# adc-peripheral.net
KiCad netlist of a schematic drawn in Altium Designer
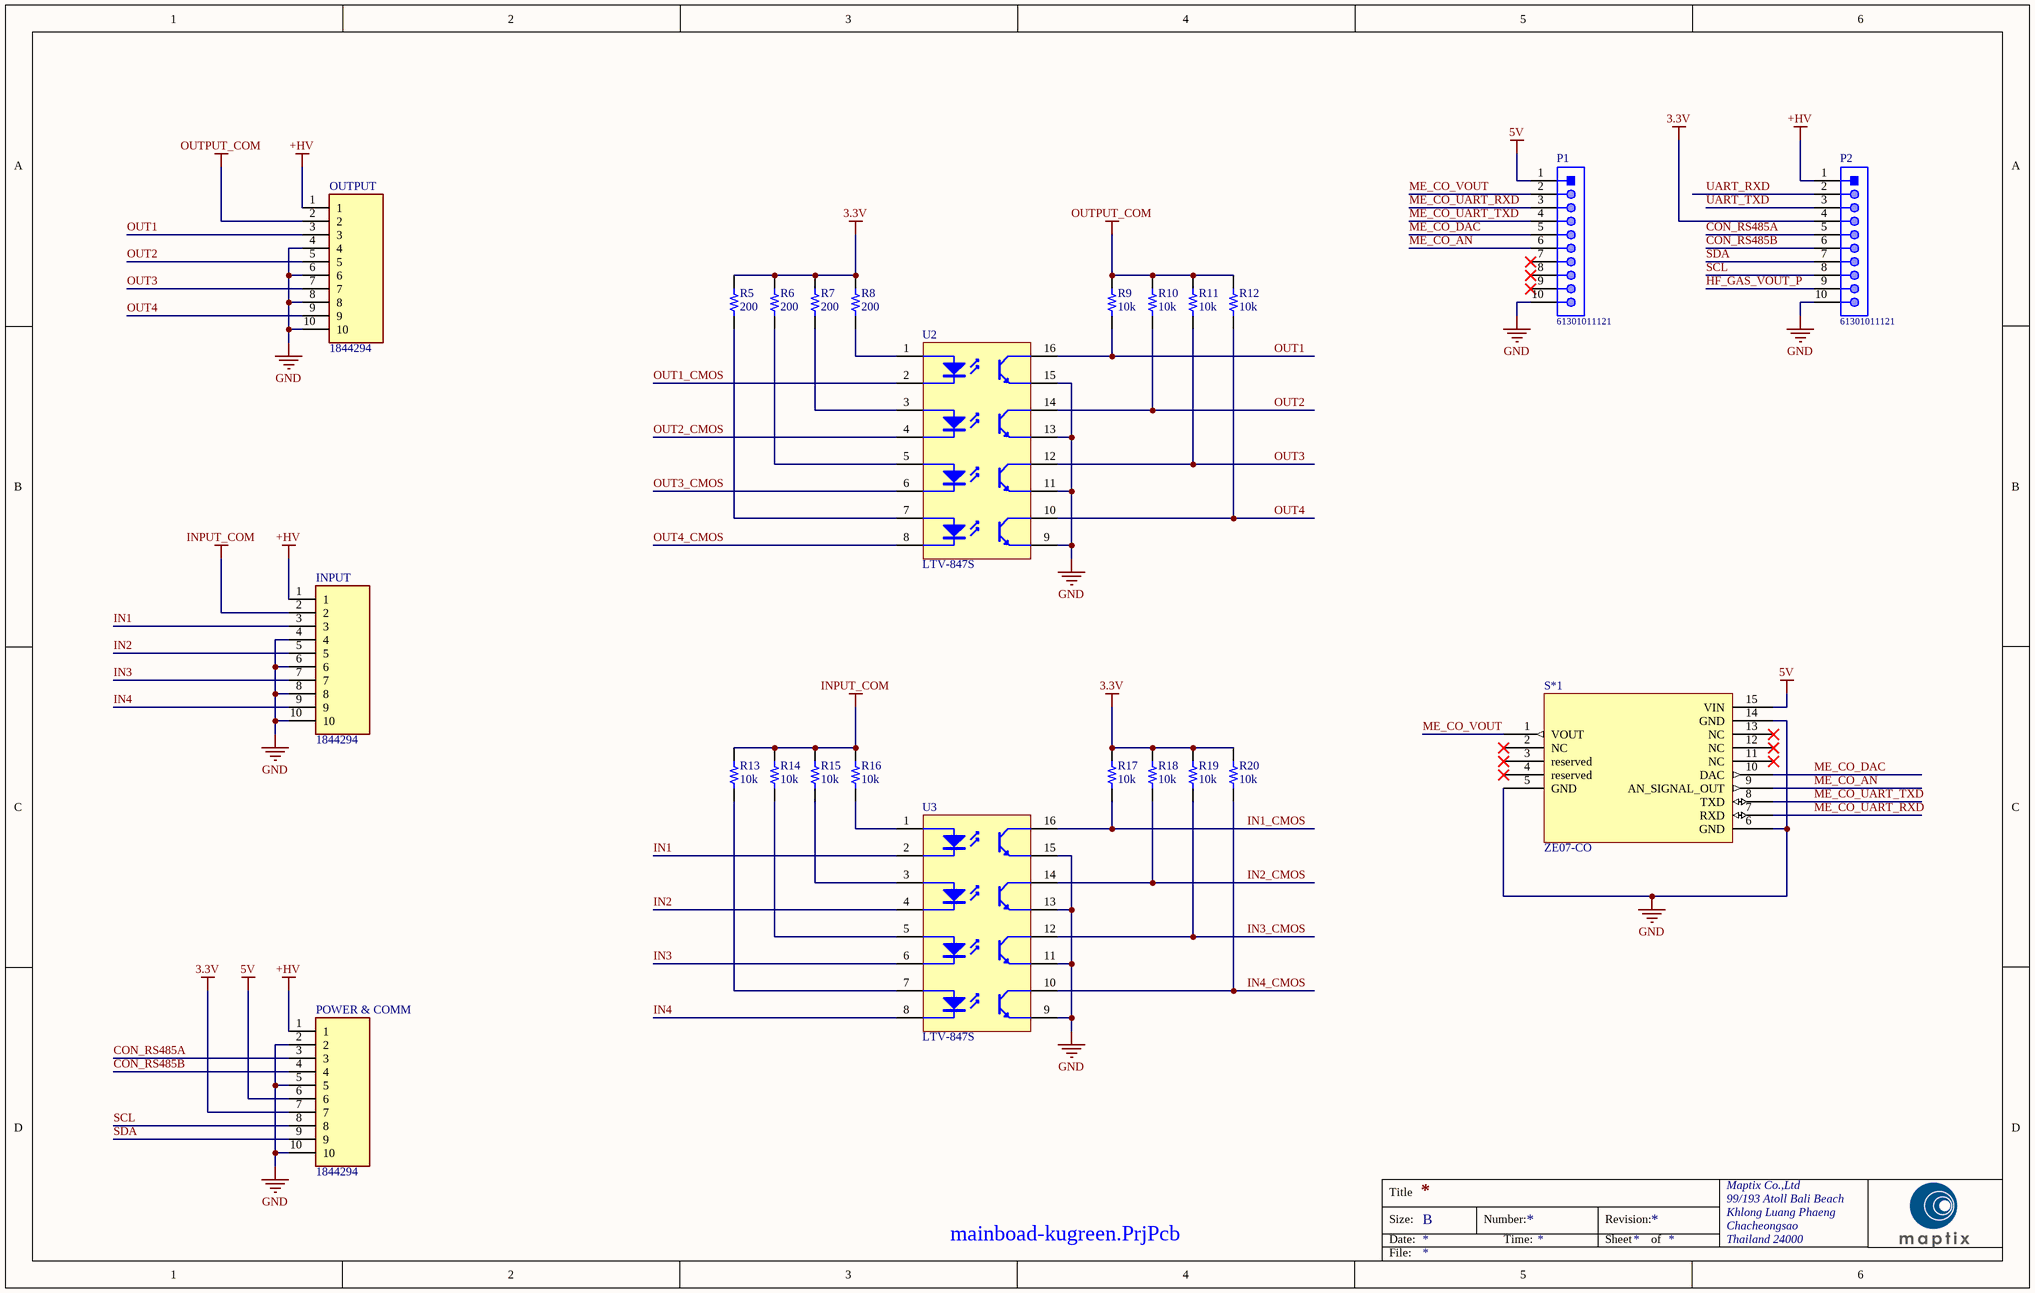
[diagram p0: adc-peripheral.SchDoc]

(export (version "E")
  (design (tool "Eeschema 10.0.6"))
  (components
    (comp (ref "INPUT")
      (value "1844294")
      (footprint "SamacSys:SHDR10W100P0X350_1X10_3640X920X725P")
      (description "Connector")
      (fields (field (name "MOUSER PART NUMBER") "651-1844294") (field (name "RS PART NUMBER") "8042267"))
      (libsource (lib "*") (part "1844294"))
    )
    (comp (ref "OUTPUT")
      (value "1844294")
      (footprint "SamacSys:SHDR10W100P0X350_1X10_3640X920X725P")
      (description "Connector")
      (fields (field (name "MOUSER PART NUMBER") "651-1844294") (field (name "RS PART NUMBER") "8042267"))
      (libsource (lib "*") (part "1844294"))
    )
    (comp (ref "P1")
      (value "61301011121")
      (footprint "61301011121")
      (description "THT Vertical Pin Header WR-PHD, Pitch 2.54 mm, Single Row, 10 pins")
      (fields (field (name "MANUFACTURER") "Wurth Elektronik") (field (name "PUBLISHER") "WurthElektronik"))
      (libsource (lib "Altium Content Vault") (part "WE-CN-1P-M-R10"))
    )
    (comp (ref "P2")
      (value "61301011121")
      (footprint "61301011121")
      (description "THT Vertical Pin Header WR-PHD, Pitch 2.54 mm, Single Row, 10 pins")
      (fields (field (name "MANUFACTURER") "Wurth Elektronik") (field (name "PUBLISHER") "WurthElektronik"))
      (libsource (lib "Altium Content Vault") (part "WE-CN-1P-M-R10"))
    )
    (comp (ref "POWER & COMM")
      (value "1844294")
      (footprint "SamacSys:SHDR10W100P0X350_1X10_3640X920X725P")
      (description "Connector")
      (fields (field (name "MOUSER PART NUMBER") "651-1844294") (field (name "RS PART NUMBER") "8042267"))
      (libsource (lib "*") (part "1844294"))
    )
    (comp (ref "R5")
      (value "200")
      (footprint "RES 0603_1608")
      (description "Resistor")
      (fields (field (name "PART NUMBER") "CRCW060329K4FKEA") (field (name "MANUFACTURER") "Vishay Dale"))
      (libsource (lib "Celestial Altium Library - altium_library") (part "Resistor"))
    )
    (comp (ref "R6")
      (value "200")
      (footprint "RES 0603_1608")
      (description "Resistor")
      (fields (field (name "PART NUMBER") "CRCW060329K4FKEA") (field (name "MANUFACTURER") "Vishay Dale"))
      (libsource (lib "Celestial Altium Library - altium_library") (part "Resistor"))
    )
    (comp (ref "R7")
      (value "200")
      (footprint "RES 0603_1608")
      (description "Resistor")
      (fields (field (name "PART NUMBER") "CRCW060329K4FKEA") (field (name "MANUFACTURER") "Vishay Dale"))
      (libsource (lib "Celestial Altium Library - altium_library") (part "Resistor"))
    )
    (comp (ref "R8")
      (value "200")
      (footprint "RES 0603_1608")
      (description "Resistor")
      (fields (field (name "PART NUMBER") "CRCW060329K4FKEA") (field (name "MANUFACTURER") "Vishay Dale"))
      (libsource (lib "Celestial Altium Library - altium_library") (part "Resistor"))
    )
    (comp (ref "R9")
      (value "10k")
      (footprint "RES 0603_1608")
      (description "Resistor")
      (fields (field (name "PART NUMBER") "CRCW060329K4FKEA") (field (name "MANUFACTURER") "Vishay Dale"))
      (libsource (lib "Celestial Altium Library - altium_library") (part "Resistor"))
    )
    (comp (ref "R10")
      (value "10k")
      (footprint "RES 0603_1608")
      (description "Resistor")
      (fields (field (name "PART NUMBER") "CRCW060329K4FKEA") (field (name "MANUFACTURER") "Vishay Dale"))
      (libsource (lib "Celestial Altium Library - altium_library") (part "Resistor"))
    )
    (comp (ref "R11")
      (value "10k")
      (footprint "RES 0603_1608")
      (description "Resistor")
      (fields (field (name "PART NUMBER") "CRCW060329K4FKEA") (field (name "MANUFACTURER") "Vishay Dale"))
      (libsource (lib "Celestial Altium Library - altium_library") (part "Resistor"))
    )
    (comp (ref "R12")
      (value "10k")
      (footprint "RES 0603_1608")
      (description "Resistor")
      (fields (field (name "PART NUMBER") "CRCW060329K4FKEA") (field (name "MANUFACTURER") "Vishay Dale"))
      (libsource (lib "Celestial Altium Library - altium_library") (part "Resistor"))
    )
    (comp (ref "R13")
      (value "10k")
      (footprint "RES 0603_1608")
      (description "Resistor")
      (fields (field (name "PART NUMBER") "CRCW060329K4FKEA") (field (name "MANUFACTURER") "Vishay Dale"))
      (libsource (lib "Celestial Altium Library - altium_library") (part "Resistor"))
    )
    (comp (ref "R14")
      (value "10k")
      (footprint "RES 0603_1608")
      (description "Resistor")
      (fields (field (name "PART NUMBER") "CRCW060329K4FKEA") (field (name "MANUFACTURER") "Vishay Dale"))
      (libsource (lib "Celestial Altium Library - altium_library") (part "Resistor"))
    )
    (comp (ref "R15")
      (value "10k")
      (footprint "RES 0603_1608")
      (description "Resistor")
      (fields (field (name "PART NUMBER") "CRCW060329K4FKEA") (field (name "MANUFACTURER") "Vishay Dale"))
      (libsource (lib "Celestial Altium Library - altium_library") (part "Resistor"))
    )
    (comp (ref "R16")
      (value "10k")
      (footprint "RES 0603_1608")
      (description "Resistor")
      (fields (field (name "PART NUMBER") "CRCW060329K4FKEA") (field (name "MANUFACTURER") "Vishay Dale"))
      (libsource (lib "Celestial Altium Library - altium_library") (part "Resistor"))
    )
    (comp (ref "R17")
      (value "10k")
      (footprint "RES 0603_1608")
      (description "Resistor")
      (fields (field (name "PART NUMBER") "CRCW060329K4FKEA") (field (name "MANUFACTURER") "Vishay Dale"))
      (libsource (lib "Celestial Altium Library - altium_library") (part "Resistor"))
    )
    (comp (ref "R18")
      (value "10k")
      (footprint "RES 0603_1608")
      (description "Resistor")
      (fields (field (name "PART NUMBER") "CRCW060329K4FKEA") (field (name "MANUFACTURER") "Vishay Dale"))
      (libsource (lib "Celestial Altium Library - altium_library") (part "Resistor"))
    )
    (comp (ref "R19")
      (value "10k")
      (footprint "RES 0603_1608")
      (description "Resistor")
      (fields (field (name "PART NUMBER") "CRCW060329K4FKEA") (field (name "MANUFACTURER") "Vishay Dale"))
      (libsource (lib "Celestial Altium Library - altium_library") (part "Resistor"))
    )
    (comp (ref "R20")
      (value "10k")
      (footprint "RES 0603_1608")
      (description "Resistor")
      (fields (field (name "PART NUMBER") "CRCW060329K4FKEA") (field (name "MANUFACTURER") "Vishay Dale"))
      (libsource (lib "Celestial Altium Library - altium_library") (part "Resistor"))
    )
    (comp (ref "S*1") (value "ZE07-CO") (footprint "ZE07-CO") (libsource (lib "pae") (part "ZE07-CO")))
    (comp (ref "U2")
      (value "LTV-847S")
      (footprint "LTST-LTV-847S_V")
      (description "Photocoupler, 50 mA, -30 to 110 degC, 16-Pin SMD, RoHS, Tube")
      (fields (field (name "MANUFACTURER") "Lite-On"))
      (libsource (lib "Altium Content Vault") (part "LTST-LTV-847-16"))
    )
    (comp (ref "U3")
      (value "LTV-847S")
      (footprint "LTST-LTV-847S_V")
      (description "Photocoupler, 50 mA, -30 to 110 degC, 16-Pin SMD, RoHS, Tube")
      (fields (field (name "MANUFACTURER") "Lite-On"))
      (libsource (lib "Altium Content Vault") (part "LTST-LTV-847-16"))
    )
  )
  (nets
    (net (code "1") (name "+HV") (class "Default")
      (node (ref "INPUT") (pin "1") (pinfunction "1_1") (pintype "passive"))
      (node (ref "OUTPUT") (pin "1") (pinfunction "1_1") (pintype "passive"))
      (node (ref "P2") (pin "1") (pinfunction "1_1") (pintype "passive"))
      (node (ref "POWER & COMM") (pin "1") (pinfunction "1_1") (pintype "passive"))
    )
    (net (code "2") (name "/CON_RS485A") (class "Default")
      (node (ref "P2") (pin "5") (pinfunction "5_5") (pintype "passive"))
      (node (ref "POWER & COMM") (pin "3") (pinfunction "3_3") (pintype "passive"))
    )
    (net (code "3") (name "/CON_RS485B") (class "Default")
      (node (ref "P2") (pin "6") (pinfunction "6_6") (pintype "passive"))
      (node (ref "POWER & COMM") (pin "4") (pinfunction "4_4") (pintype "passive"))
    )
    (net (code "4") (name "/HF_GAS_VOUT_P") (class "Default")
      (node (ref "P2") (pin "9") (pinfunction "9_9") (pintype "passive"))
    )
    (net (code "5") (name "/IN1") (class "Default")
      (node (ref "INPUT") (pin "3") (pinfunction "3_3") (pintype "passive"))
      (node (ref "U3") (pin "2") (pinfunction "Cathode1_2") (pintype "passive"))
    )
    (net (code "6") (name "/IN1_CMOS") (class "Default")
      (node (ref "R17") (pin "1") (pinfunction "1_1") (pintype "passive"))
      (node (ref "U3") (pin "16") (pinfunction "Collector1_16") (pintype "passive"))
    )
    (net (code "7") (name "/IN2") (class "Default")
      (node (ref "INPUT") (pin "5") (pinfunction "5_5") (pintype "passive"))
      (node (ref "U3") (pin "4") (pinfunction "Cathode2_4") (pintype "passive"))
    )
    (net (code "8") (name "/IN2_CMOS") (class "Default")
      (node (ref "R18") (pin "1") (pinfunction "1_1") (pintype "passive"))
      (node (ref "U3") (pin "14") (pinfunction "Collector2_14") (pintype "passive"))
    )
    (net (code "9") (name "/IN3") (class "Default")
      (node (ref "INPUT") (pin "7") (pinfunction "7_7") (pintype "passive"))
      (node (ref "U3") (pin "6") (pinfunction "Cathode3_6") (pintype "passive"))
    )
    (net (code "10") (name "/IN3_CMOS") (class "Default")
      (node (ref "R19") (pin "1") (pinfunction "1_1") (pintype "passive"))
      (node (ref "U3") (pin "12") (pinfunction "Collector3_12") (pintype "passive"))
    )
    (net (code "11") (name "/IN4") (class "Default")
      (node (ref "INPUT") (pin "9") (pinfunction "9_9") (pintype "passive"))
      (node (ref "U3") (pin "8") (pinfunction "Cathode4_8") (pintype "passive"))
    )
    (net (code "12") (name "/IN4_CMOS") (class "Default")
      (node (ref "R20") (pin "1") (pinfunction "1_1") (pintype "passive"))
      (node (ref "U3") (pin "10") (pinfunction "Collector4_10") (pintype "passive"))
    )
    (net (code "13") (name "/ME_CO_AN") (class "Default")
      (node (ref "P1") (pin "6") (pinfunction "6_6") (pintype "passive"))
      (node (ref "S*1") (pin "9") (pinfunction "AN_SIGNAL_OUT_9") (pintype "output"))
    )
    (net (code "14") (name "/ME_CO_DAC") (class "Default")
      (node (ref "P1") (pin "5") (pinfunction "5_5") (pintype "passive"))
      (node (ref "S*1") (pin "10") (pinfunction "DAC_10") (pintype "output"))
    )
    (net (code "15") (name "/ME_CO_UART_RXD") (class "Default")
      (node (ref "P1") (pin "3") (pinfunction "3_3") (pintype "passive"))
      (node (ref "S*1") (pin "7") (pinfunction "RXD_7") (pintype "bidirectional"))
    )
    (net (code "16") (name "/ME_CO_UART_TXD") (class "Default")
      (node (ref "P1") (pin "4") (pinfunction "4_4") (pintype "passive"))
      (node (ref "S*1") (pin "8") (pinfunction "TXD_8") (pintype "bidirectional"))
    )
    (net (code "17") (name "/ME_CO_VOUT") (class "Default")
      (node (ref "P1") (pin "2") (pinfunction "2_2") (pintype "passive"))
      (node (ref "S*1") (pin "1") (pinfunction "VOUT_1") (pintype "output"))
    )
    (net (code "18") (name "/OUT1") (class "Default")
      (node (ref "OUTPUT") (pin "3") (pinfunction "3_3") (pintype "passive"))
      (node (ref "R9") (pin "1") (pinfunction "1_1") (pintype "passive"))
      (node (ref "U2") (pin "16") (pinfunction "Collector1_16") (pintype "passive"))
    )
    (net (code "19") (name "/OUT1_CMOS") (class "Default")
      (node (ref "U2") (pin "2") (pinfunction "Cathode1_2") (pintype "passive"))
    )
    (net (code "20") (name "/OUT2") (class "Default")
      (node (ref "OUTPUT") (pin "5") (pinfunction "5_5") (pintype "passive"))
      (node (ref "R10") (pin "1") (pinfunction "1_1") (pintype "passive"))
      (node (ref "U2") (pin "14") (pinfunction "Collector2_14") (pintype "passive"))
    )
    (net (code "21") (name "/OUT2_CMOS") (class "Default")
      (node (ref "U2") (pin "4") (pinfunction "Cathode2_4") (pintype "passive"))
    )
    (net (code "22") (name "/OUT3") (class "Default")
      (node (ref "OUTPUT") (pin "7") (pinfunction "7_7") (pintype "passive"))
      (node (ref "R11") (pin "1") (pinfunction "1_1") (pintype "passive"))
      (node (ref "U2") (pin "12") (pinfunction "Collector3_12") (pintype "passive"))
    )
    (net (code "23") (name "/OUT3_CMOS") (class "Default")
      (node (ref "U2") (pin "6") (pinfunction "Cathode3_6") (pintype "passive"))
    )
    (net (code "24") (name "/OUT4") (class "Default")
      (node (ref "OUTPUT") (pin "9") (pinfunction "9_9") (pintype "passive"))
      (node (ref "R12") (pin "1") (pinfunction "1_1") (pintype "passive"))
      (node (ref "U2") (pin "10") (pinfunction "Collector4_10") (pintype "passive"))
    )
    (net (code "25") (name "/OUT4_CMOS") (class "Default")
      (node (ref "U2") (pin "8") (pinfunction "Cathode4_8") (pintype "passive"))
    )
    (net (code "26") (name "/SCL") (class "Default")
      (node (ref "P2") (pin "8") (pinfunction "8_8") (pintype "passive"))
      (node (ref "POWER & COMM") (pin "8") (pinfunction "8_8") (pintype "passive"))
    )
    (net (code "27") (name "/SDA") (class "Default")
      (node (ref "P2") (pin "7") (pinfunction "7_7") (pintype "passive"))
      (node (ref "POWER & COMM") (pin "9") (pinfunction "9_9") (pintype "passive"))
    )
    (net (code "28") (name "/UART_RXD") (class "Default")
      (node (ref "P2") (pin "2") (pinfunction "2_2") (pintype "passive"))
    )
    (net (code "29") (name "/UART_TXD") (class "Default")
      (node (ref "P2") (pin "3") (pinfunction "3_3") (pintype "passive"))
    )
    (net (code "30") (name "3.3V") (class "Default")
      (node (ref "P2") (pin "4") (pinfunction "4_4") (pintype "passive"))
      (node (ref "POWER & COMM") (pin "7") (pinfunction "7_7") (pintype "passive"))
      (node (ref "R17") (pin "2") (pinfunction "2_2") (pintype "passive"))
      (node (ref "R18") (pin "2") (pinfunction "2_2") (pintype "passive"))
      (node (ref "R19") (pin "2") (pinfunction "2_2") (pintype "passive"))
      (node (ref "R20") (pin "2") (pinfunction "2_2") (pintype "passive"))
      (node (ref "R5") (pin "2") (pinfunction "2_2") (pintype "passive"))
      (node (ref "R6") (pin "2") (pinfunction "2_2") (pintype "passive"))
      (node (ref "R7") (pin "2") (pinfunction "2_2") (pintype "passive"))
      (node (ref "R8") (pin "2") (pinfunction "2_2") (pintype "passive"))
    )
    (net (code "31") (name "5V") (class "Default")
      (node (ref "P1") (pin "1") (pinfunction "1_1") (pintype "passive"))
      (node (ref "POWER & COMM") (pin "6") (pinfunction "6_6") (pintype "passive"))
      (node (ref "S*1") (pin "15") (pinfunction "VIN_15") (pintype "power_in"))
    )
    (net (code "32") (name "GND") (class "Default")
      (node (ref "INPUT") (pin "10") (pinfunction "10_10") (pintype "passive"))
      (node (ref "INPUT") (pin "4") (pinfunction "4_4") (pintype "passive"))
      (node (ref "INPUT") (pin "6") (pinfunction "6_6") (pintype "passive"))
      (node (ref "INPUT") (pin "8") (pinfunction "8_8") (pintype "passive"))
      (node (ref "OUTPUT") (pin "10") (pinfunction "10_10") (pintype "passive"))
      (node (ref "OUTPUT") (pin "4") (pinfunction "4_4") (pintype "passive"))
      (node (ref "OUTPUT") (pin "6") (pinfunction "6_6") (pintype "passive"))
      (node (ref "OUTPUT") (pin "8") (pinfunction "8_8") (pintype "passive"))
      (node (ref "P1") (pin "10") (pinfunction "10_10") (pintype "passive"))
      (node (ref "P2") (pin "10") (pinfunction "10_10") (pintype "passive"))
      (node (ref "POWER & COMM") (pin "10") (pinfunction "10_10") (pintype "passive"))
      (node (ref "POWER & COMM") (pin "2") (pinfunction "2_2") (pintype "passive"))
      (node (ref "POWER & COMM") (pin "5") (pinfunction "5_5") (pintype "passive"))
      (node (ref "S*1") (pin "14") (pinfunction "GND_14") (pintype "power_in"))
      (node (ref "S*1") (pin "5") (pinfunction "GND_5") (pintype "power_in"))
      (node (ref "S*1") (pin "6") (pinfunction "GND_6") (pintype "power_in"))
      (node (ref "U2") (pin "11") (pinfunction "Emitter3_11") (pintype "passive"))
      (node (ref "U2") (pin "13") (pinfunction "Emitter2_13") (pintype "passive"))
      (node (ref "U2") (pin "15") (pinfunction "Emitter1_15") (pintype "passive"))
      (node (ref "U2") (pin "9") (pinfunction "Emitter4_9") (pintype "passive"))
      (node (ref "U3") (pin "11") (pinfunction "Emitter3_11") (pintype "passive"))
      (node (ref "U3") (pin "13") (pinfunction "Emitter2_13") (pintype "passive"))
      (node (ref "U3") (pin "15") (pinfunction "Emitter1_15") (pintype "passive"))
      (node (ref "U3") (pin "9") (pinfunction "Emitter4_9") (pintype "passive"))
    )
    (net (code "33") (name "INPUT_COM") (class "Default")
      (node (ref "INPUT") (pin "2") (pinfunction "2_2") (pintype "passive"))
      (node (ref "R13") (pin "2") (pinfunction "2_2") (pintype "passive"))
      (node (ref "R14") (pin "2") (pinfunction "2_2") (pintype "passive"))
      (node (ref "R15") (pin "2") (pinfunction "2_2") (pintype "passive"))
      (node (ref "R16") (pin "2") (pinfunction "2_2") (pintype "passive"))
    )
    (net (code "34") (name "Net-(U2-Anode1)") (class "Default")
      (node (ref "R8") (pin "1") (pinfunction "1_1") (pintype "passive"))
      (node (ref "U2") (pin "1") (pinfunction "Anode1_1") (pintype "passive"))
    )
    (net (code "35") (name "Net-(U2-Anode2)") (class "Default")
      (node (ref "R7") (pin "1") (pinfunction "1_1") (pintype "passive"))
      (node (ref "U2") (pin "3") (pinfunction "Anode2_3") (pintype "passive"))
    )
    (net (code "36") (name "Net-(U2-Anode3)") (class "Default")
      (node (ref "R6") (pin "1") (pinfunction "1_1") (pintype "passive"))
      (node (ref "U2") (pin "5") (pinfunction "Anode3_5") (pintype "passive"))
    )
    (net (code "37") (name "Net-(U2-Anode4)") (class "Default")
      (node (ref "R5") (pin "1") (pinfunction "1_1") (pintype "passive"))
      (node (ref "U2") (pin "7") (pinfunction "Anode4_7") (pintype "passive"))
    )
    (net (code "38") (name "Net-(U3-Anode1)") (class "Default")
      (node (ref "R16") (pin "1") (pinfunction "1_1") (pintype "passive"))
      (node (ref "U3") (pin "1") (pinfunction "Anode1_1") (pintype "passive"))
    )
    (net (code "39") (name "Net-(U3-Anode2)") (class "Default")
      (node (ref "R15") (pin "1") (pinfunction "1_1") (pintype "passive"))
      (node (ref "U3") (pin "3") (pinfunction "Anode2_3") (pintype "passive"))
    )
    (net (code "40") (name "Net-(U3-Anode3)") (class "Default")
      (node (ref "R14") (pin "1") (pinfunction "1_1") (pintype "passive"))
      (node (ref "U3") (pin "5") (pinfunction "Anode3_5") (pintype "passive"))
    )
    (net (code "41") (name "Net-(U3-Anode4)") (class "Default")
      (node (ref "R13") (pin "1") (pinfunction "1_1") (pintype "passive"))
      (node (ref "U3") (pin "7") (pinfunction "Anode4_7") (pintype "passive"))
    )
    (net (code "42") (name "OUTPUT_COM") (class "Default")
      (node (ref "OUTPUT") (pin "2") (pinfunction "2_2") (pintype "passive"))
      (node (ref "R10") (pin "2") (pinfunction "2_2") (pintype "passive"))
      (node (ref "R11") (pin "2") (pinfunction "2_2") (pintype "passive"))
      (node (ref "R12") (pin "2") (pinfunction "2_2") (pintype "passive"))
      (node (ref "R9") (pin "2") (pinfunction "2_2") (pintype "passive"))
    )
    (net (code "43") (name "unconnected-(P1-Pad7)") (class "Default")
      (node (ref "P1") (pin "7") (pinfunction "7_7") (pintype "passive+no_connect"))
    )
    (net (code "44") (name "unconnected-(P1-Pad8)") (class "Default")
      (node (ref "P1") (pin "8") (pinfunction "8_8") (pintype "passive+no_connect"))
    )
    (net (code "45") (name "unconnected-(P1-Pad9)") (class "Default")
      (node (ref "P1") (pin "9") (pinfunction "9_9") (pintype "passive+no_connect"))
    )
    (net (code "46") (name "unconnected-(S*1-NC-Pad2)") (class "Default")
      (node (ref "S*1") (pin "2") (pinfunction "NC_2") (pintype "passive+no_connect"))
    )
    (net (code "47") (name "unconnected-(S*1-NC-Pad11)") (class "Default")
      (node (ref "S*1") (pin "11") (pinfunction "NC_11") (pintype "passive+no_connect"))
    )
    (net (code "48") (name "unconnected-(S*1-NC-Pad12)") (class "Default")
      (node (ref "S*1") (pin "12") (pinfunction "NC_12") (pintype "passive+no_connect"))
    )
    (net (code "49") (name "unconnected-(S*1-NC-Pad13)") (class "Default")
      (node (ref "S*1") (pin "13") (pinfunction "NC_13") (pintype "passive+no_connect"))
    )
    (net (code "50") (name "unconnected-(S*1-reserved-Pad3)") (class "Default")
      (node (ref "S*1") (pin "3") (pinfunction "reserved_3") (pintype "passive+no_connect"))
    )
    (net (code "51") (name "unconnected-(S*1-reserved-Pad4)") (class "Default")
      (node (ref "S*1") (pin "4") (pinfunction "reserved_4") (pintype "passive+no_connect"))
    )
  )
)
